# Sheet1.net
KiCad netlist of a schematic drawn in Altium Designer
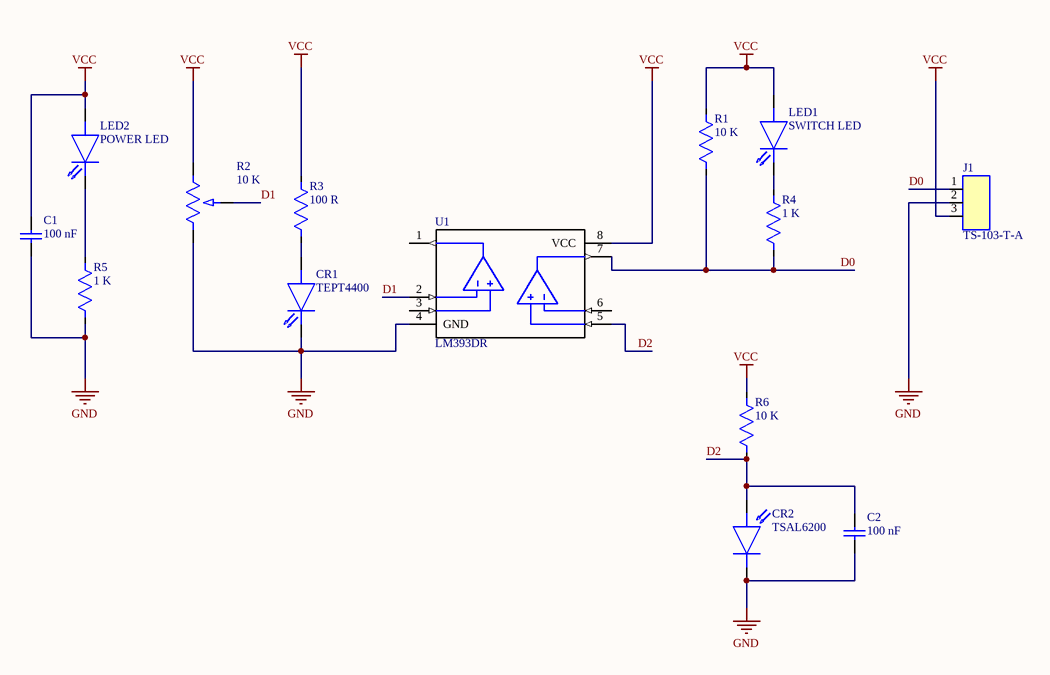
[diagram p0: Sheet1.SchDoc]

(export (version "E")
  (design (tool "Eeschema 10.0.6"))
  (components
    (comp (ref "C1")
      (value "100 nF")
      (footprint "C0805C104M8RAC7800")
      (description "CAP CER 0.1UF 10V X7R 0805")
      (libsource (lib "Integrated_Library1") (part "C0805C104M8RACTU"))
    )
    (comp (ref "C2")
      (value "100 nF")
      (footprint "C0805C104M8RAC7800")
      (description "CAP CER 0.1UF 10V X7R 0805")
      (libsource (lib "Integrated_Library1") (part "C0805C104M8RACTU"))
    )
    (comp (ref "CR1")
      (value "TEPT4400")
      (footprint "TEPT4400")
      (description "Phototransistors 570nm Top View Radial")
      (libsource (lib "Integrated_Library1") (part "TEPT4400"))
    )
    (comp (ref "CR2")
      (value "TSAL6200")
      (footprint "TSAL6200")
      (description "Infrared (IR) Emitter 940nm 1.35V 100mA 40mW/sr @ 100mA 34° Radial, 5mm Dia (T 1 3/4)")
      (libsource (lib "Schlib3") (part "TSAL6200"))
    )
    (comp (ref "J1")
      (value "TS-103-T-A")
      (footprint "TS-103-T-A")
      (description "No Description Available")
      (libsource (lib "Integrated_Library1") (part "TS-103-T-A"))
    )
    (comp (ref "LED1")
      (value "SWITCH LED")
      (footprint "CMD15-21VRD/TR8")
      (description "Red LED Indication - Discrete 1.7V 1206 (3216 Metric)")
      (libsource (lib "Integrated_Library1") (part "CMD15-21VRDTR8"))
    )
    (comp (ref "LED2")
      (value "POWER LED")
      (footprint "CMD15-21VRD/TR8")
      (description "Red LED Indication - Discrete 1.7V 1206 (3216 Metric)")
      (libsource (lib "Integrated_Library1") (part "CMD15-21VRDTR8"))
    )
    (comp (ref "R1")
      (value "10 K")
      (footprint "ERJ-6GEYJ103V")
      (description "10 kOhms ±5% 0.125W, 1/8W Chip Resistor 0805 (2012 Metric) Automotive AEC-Q200 Thick Film")
      (libsource (lib "Integrated_Library1") (part "ERJ-6GEYJ103V"))
    )
    (comp (ref "R2")
      (value "10 K")
      (footprint "3296W-1-103LF")
      (description "10 kOhms 0.5W, 1/2W PC Pins Through Hole Trimmer Potentiometer Cermet 25.0 Turn Top Adjustment")
      (libsource (lib "Integrated_Library1") (part "3296W-1-103LF"))
    )
    (comp (ref "R3")
      (value "100 R")
      (footprint "RC0805N_PAN")
      (description "RES SMD 100 OHM 0.1% 1/8W 0805")
      (libsource (lib "Integrated_Library1") (part "ERA-6AEB101V"))
    )
    (comp (ref "R4")
      (value "1 K")
      (footprint "RNCF0805TKY1K00")
      (description "RES SMD 1K OHM 0.01% 1/8W 0805")
      (libsource (lib "Integrated_Library1") (part "RNCF0805TKY1K00"))
    )
    (comp (ref "R5")
      (value "1 K")
      (footprint "RNCF0805TKY1K00")
      (description "RES SMD 1K OHM 0.01% 1/8W 0805")
      (libsource (lib "Integrated_Library1") (part "RNCF0805TKY1K00"))
    )
    (comp (ref "R6")
      (value "10 K")
      (footprint "ERJ-6GEYJ103V")
      (description "10 kOhms ±5% 0.125W, 1/8W Chip Resistor 0805 (2012 Metric) Automotive AEC-Q200 Thick Film")
      (libsource (lib "Integrated_Library1") (part "ERJ-6GEYJ103V"))
    )
    (comp (ref "U1")
      (value "LM393DR")
      (footprint "LM393DR")
      (description "IC COMPARATOR 2 DIFF 8SOIC")
      (libsource (lib "Integrated_Library1") (part "LM393DR"))
    )
  )
  (nets
    (net (code "1") (name "/D0") (class "Default")
      (node (ref "J1") (pin "1") (pinfunction "1_1") (pintype "passive"))
      (node (ref "R1") (pin "1") (pinfunction "1_1") (pintype "passive"))
      (node (ref "R4") (pin "1") (pinfunction "1_1") (pintype "passive"))
      (node (ref "U1") (pin "7") (pinfunction "OUT2_7") (pintype "output"))
    )
    (net (code "2") (name "/D1") (class "Default")
      (node (ref "R2") (pin "2") (pinfunction "2_2") (pintype "passive"))
      (node (ref "U1") (pin "2") (pinfunction "1IN-_2") (pintype "input"))
    )
    (net (code "3") (name "/D2") (class "Default")
      (node (ref "C2") (pin "2") (pinfunction "2_2") (pintype "passive"))
      (node (ref "CR2") (pin "1") (pinfunction "1_1") (pintype "passive"))
      (node (ref "R6") (pin "1") (pinfunction "1_1") (pintype "passive"))
      (node (ref "U1") (pin "5") (pinfunction "2IN+_5") (pintype "input"))
    )
    (net (code "4") (name "GND") (class "Default")
      (node (ref "C1") (pin "1") (pinfunction "1_1") (pintype "passive"))
      (node (ref "C2") (pin "1") (pinfunction "1_1") (pintype "passive"))
      (node (ref "CR1") (pin "2") (pinfunction "2_2") (pintype "passive"))
      (node (ref "CR2") (pin "2") (pinfunction "2_2") (pintype "passive"))
      (node (ref "J1") (pin "2") (pinfunction "2_2") (pintype "passive"))
      (node (ref "R2") (pin "3") (pinfunction "3_3") (pintype "passive"))
      (node (ref "R5") (pin "1") (pinfunction "1_1") (pintype "passive"))
      (node (ref "U1") (pin "4") (pinfunction "GND_4") (pintype "power_in"))
    )
    (net (code "5") (name "Net-(CR1-Pad1)") (class "Default")
      (node (ref "CR1") (pin "1") (pinfunction "1_1") (pintype "passive"))
      (node (ref "R3") (pin "1") (pinfunction "1_1") (pintype "passive"))
    )
    (net (code "6") (name "Net-(LED1-Pad2)") (class "Default")
      (node (ref "LED1") (pin "2") (pinfunction "2_2") (pintype "passive"))
      (node (ref "R4") (pin "2") (pinfunction "2_2") (pintype "passive"))
    )
    (net (code "7") (name "Net-(LED2-Pad2)") (class "Default")
      (node (ref "LED2") (pin "2") (pinfunction "2_2") (pintype "passive"))
      (node (ref "R5") (pin "2") (pinfunction "2_2") (pintype "passive"))
    )
    (net (code "8") (name "VCC") (class "Default")
      (node (ref "C1") (pin "2") (pinfunction "2_2") (pintype "passive"))
      (node (ref "J1") (pin "3") (pinfunction "3_3") (pintype "passive"))
      (node (ref "LED1") (pin "1") (pinfunction "1_1") (pintype "passive"))
      (node (ref "LED2") (pin "1") (pinfunction "1_1") (pintype "passive"))
      (node (ref "R1") (pin "2") (pinfunction "2_2") (pintype "passive"))
      (node (ref "R2") (pin "1") (pinfunction "1_1") (pintype "passive"))
      (node (ref "R3") (pin "2") (pinfunction "2_2") (pintype "passive"))
      (node (ref "R6") (pin "2") (pinfunction "2_2") (pintype "passive"))
      (node (ref "U1") (pin "8") (pinfunction "VCC_8") (pintype "power_in"))
    )
    (net (code "9") (name "unconnected-(U1-1IN+-Pad3)") (class "Default")
      (node (ref "U1") (pin "3") (pinfunction "1IN+_3") (pintype "input"))
    )
    (net (code "10") (name "unconnected-(U1-2IN--Pad6)") (class "Default")
      (node (ref "U1") (pin "6") (pinfunction "2IN-_6") (pintype "input"))
    )
    (net (code "11") (name "unconnected-(U1-OUT1-Pad1)") (class "Default")
      (node (ref "U1") (pin "1") (pinfunction "OUT1_1") (pintype "output"))
    )
  )
)
